# ADC_DAC_Supply.net
KiCad netlist of a schematic drawn in Altium Designer
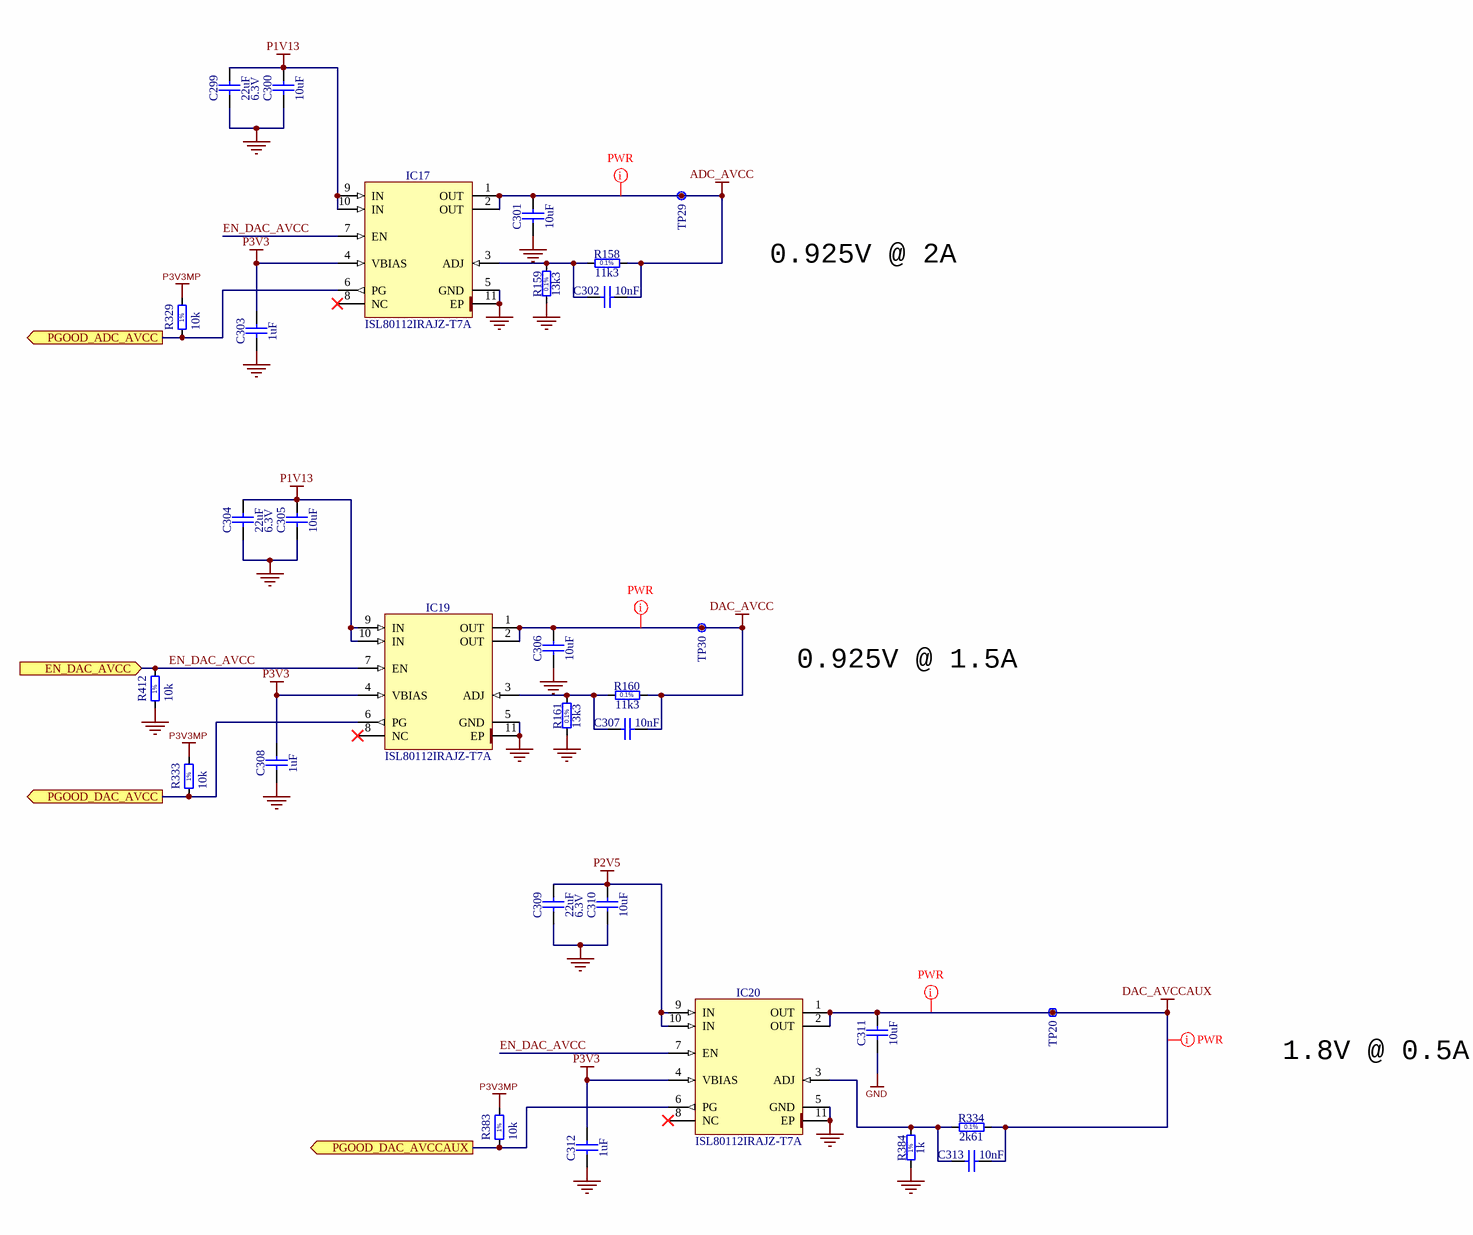
[diagram p0: ADC_DAC_Supply.SchDoc]

(export (version "E")
  (design (tool "Eeschema 10.0.6"))
  (components
    (comp (ref "C299")
      (value "22uF")
      (footprint "CAPC1709X100N")
      (description "Non-polarised capacitor")
      (fields
        (field (name "PART NUMBER") "CC0603_22UF_6.3V_20%_X5R")
        (field (name "VOLTAGE") "6.3V")
        (field (name "TOLERANCE") "±20%")
        (field (name "AUTHOR") "CERN DEM JLC")
      )
      (libsource (lib "Capacitors") (part "Capacitor - non polarized"))
    )
    (comp (ref "C300")
      (value "10uF")
      (footprint "CAPC1608X80N")
      (description "Non-polarised capacitor")
      (fields
        (field (name "PART NUMBER") "CC0603_10UF_10V_10%_X5R")
        (field (name "VOLTAGE") "10V")
        (field (name "AUTHOR") "CERN DEM JLC")
      )
      (libsource (lib "Capacitors") (part "Capacitor - non polarized"))
    )
    (comp (ref "C301")
      (value "10uF")
      (footprint "CAPC1608X80N")
      (description "Non-polarised capacitor")
      (fields
        (field (name "PART NUMBER") "CC0603_10UF_10V_10%_X5R")
        (field (name "VOLTAGE") "10V")
        (field (name "AUTHOR") "CERN DEM JLC")
      )
      (libsource (lib "Capacitors") (part "Capacitor - non polarized"))
    )
    (comp (ref "C302")
      (value "10nF")
      (footprint "CAPC1005X55N")
      (description "Non-polarised capacitor")
      (fields
        (field (name "PART NUMBER") "CC0402_10NF_25V_10%_X7R")
        (field (name "VOLTAGE") "25V")
        (field (name "AUTHOR") "CERN DEM JLC")
      )
      (libsource (lib "Capacitors") (part "Capacitor - non polarized"))
    )
    (comp (ref "C303")
      (value "1uF")
      (footprint "CAPC1005X55N")
      (description "Non-polarised capacitor")
      (fields
        (field (name "PART NUMBER") "CC0402_1UF_16V_10%_X5R")
        (field (name "VOLTAGE") "16V")
        (field (name "AUTHOR") "CERN DEM JLC")
      )
      (libsource (lib "Capacitors") (part "Capacitor - non polarized"))
    )
    (comp (ref "C304")
      (value "22uF")
      (footprint "CAPC1709X100N")
      (description "Non-polarised capacitor")
      (fields
        (field (name "PART NUMBER") "CC0603_22UF_6.3V_20%_X5R")
        (field (name "VOLTAGE") "6.3V")
        (field (name "TOLERANCE") "±20%")
        (field (name "AUTHOR") "CERN DEM JLC")
      )
      (libsource (lib "Capacitors") (part "Capacitor - non polarized"))
    )
    (comp (ref "C305")
      (value "10uF")
      (footprint "CAPC1608X80N")
      (description "Non-polarised capacitor")
      (fields
        (field (name "PART NUMBER") "CC0603_10UF_10V_10%_X5R")
        (field (name "VOLTAGE") "10V")
        (field (name "AUTHOR") "CERN DEM JLC")
      )
      (libsource (lib "Capacitors") (part "Capacitor - non polarized"))
    )
    (comp (ref "C306")
      (value "10uF")
      (footprint "CAPC1608X80N")
      (description "Non-polarised capacitor")
      (fields
        (field (name "PART NUMBER") "CC0603_10UF_10V_10%_X5R")
        (field (name "VOLTAGE") "10V")
        (field (name "AUTHOR") "CERN DEM JLC")
      )
      (libsource (lib "Capacitors") (part "Capacitor - non polarized"))
    )
    (comp (ref "C307")
      (value "10nF")
      (footprint "CAPC1005X55N")
      (description "Non-polarised capacitor")
      (fields
        (field (name "PART NUMBER") "CC0402_10NF_25V_10%_X7R")
        (field (name "VOLTAGE") "25V")
        (field (name "AUTHOR") "CERN DEM JLC")
      )
      (libsource (lib "Capacitors") (part "Capacitor - non polarized"))
    )
    (comp (ref "C308")
      (value "1uF")
      (footprint "CAPC1005X55N")
      (description "Non-polarised capacitor")
      (fields
        (field (name "PART NUMBER") "CC0402_1UF_16V_10%_X5R")
        (field (name "VOLTAGE") "16V")
        (field (name "AUTHOR") "CERN DEM JLC")
      )
      (libsource (lib "Capacitors") (part "Capacitor - non polarized"))
    )
    (comp (ref "C309")
      (value "22uF")
      (footprint "CAPC1709X100N")
      (description "Non-polarised capacitor")
      (fields
        (field (name "PART NUMBER") "CC0603_22UF_6.3V_20%_X5R")
        (field (name "VOLTAGE") "6.3V")
        (field (name "TOLERANCE") "±20%")
        (field (name "AUTHOR") "CERN DEM JLC")
      )
      (libsource (lib "Capacitors") (part "Capacitor - non polarized"))
    )
    (comp (ref "C310")
      (value "10uF")
      (footprint "CAPC1608X80N")
      (description "Non-polarised capacitor")
      (fields
        (field (name "PART NUMBER") "CC0603_10UF_10V_10%_X5R")
        (field (name "VOLTAGE") "10V")
        (field (name "AUTHOR") "CERN DEM JLC")
      )
      (libsource (lib "Capacitors") (part "Capacitor - non polarized"))
    )
    (comp (ref "C311")
      (value "10uF")
      (footprint "CAPC1608X80N")
      (description "Non-polarised capacitor")
      (fields
        (field (name "PART NUMBER") "CC0603_10UF_10V_10%_X5R")
        (field (name "VOLTAGE") "10V")
        (field (name "AUTHOR") "CERN DEM JLC")
      )
      (libsource (lib "Capacitors") (part "Capacitor - non polarized"))
    )
    (comp (ref "C312")
      (value "1uF")
      (footprint "CAPC1005X55N")
      (description "Non-polarised capacitor")
      (fields
        (field (name "PART NUMBER") "CC0402_1UF_16V_10%_X5R")
        (field (name "VOLTAGE") "16V")
        (field (name "AUTHOR") "CERN DEM JLC")
      )
      (libsource (lib "Capacitors") (part "Capacitor - non polarized"))
    )
    (comp (ref "C313")
      (value "10nF")
      (footprint "CAPC1005X55N")
      (description "Non-polarised capacitor")
      (fields
        (field (name "PART NUMBER") "CC0402_10NF_25V_10%_X7R")
        (field (name "VOLTAGE") "25V")
        (field (name "AUTHOR") "CERN DEM JLC")
      )
      (libsource (lib "Capacitors") (part "Capacitor - non polarized"))
    )
    (comp (ref "IC17")
      (value "ISL80112IRAJZ-T7A")
      (footprint "RENESAS_L10.3X3")
      (description "Ultra Low Dropout Low Input Voltage NMOS LDO Regulator")
      (fields (field (name "MANUFACTURER") "RENESAS ELECTRONICS") (field (name "AUTHOR") "CERN DEM JLC"))
      (libsource (lib "ICs And Semiconductors") (part "ISL8011x"))
    )
    (comp (ref "IC19")
      (value "ISL80112IRAJZ-T7A")
      (footprint "RENESAS_L10.3X3")
      (description "Ultra Low Dropout Low Input Voltage NMOS LDO Regulator")
      (fields (field (name "MANUFACTURER") "RENESAS ELECTRONICS") (field (name "AUTHOR") "CERN DEM JLC"))
      (libsource (lib "ICs And Semiconductors") (part "ISL8011x"))
    )
    (comp (ref "IC20")
      (value "ISL80112IRAJZ-T7A")
      (footprint "RENESAS_L10.3X3")
      (description "Ultra Low Dropout Low Input Voltage NMOS LDO Regulator")
      (fields (field (name "MANUFACTURER") "RENESAS ELECTRONICS") (field (name "AUTHOR") "CERN DEM JLC"))
      (libsource (lib "ICs And Semiconductors") (part "ISL8011x"))
    )
    (comp (ref "R158")
      (value "11k3")
      (footprint "RESC2012X60N")
      (description "Resistor - 0.1%")
      (fields
        (field (name "PART NUMBER") "R0805_11K3_0.1%_0.1W_10PPM")
        (field (name "POWER") "0.1W")
        (field (name "AUTHOR") "CERN DEM JLC")
      )
      (libsource (lib "Resistors") (part "Resistor - 0.1%"))
    )
    (comp (ref "R159")
      (value "13k3")
      (footprint "RESC2012X60N")
      (description "Resistor - 0.1%")
      (fields
        (field (name "PART NUMBER") "R0805_13K3_0.1%_0.1W_10PPM")
        (field (name "POWER") "0.1W")
        (field (name "AUTHOR") "CERN DEM JLC")
      )
      (libsource (lib "Resistors") (part "Resistor - 0.1%"))
    )
    (comp (ref "R160")
      (value "11k3")
      (footprint "RESC2012X60N")
      (description "Resistor - 0.1%")
      (fields
        (field (name "PART NUMBER") "R0805_11K3_0.1%_0.1W_10PPM")
        (field (name "POWER") "0.1W")
        (field (name "AUTHOR") "CERN DEM JLC")
      )
      (libsource (lib "Resistors") (part "Resistor - 0.1%"))
    )
    (comp (ref "R161")
      (value "13k3")
      (footprint "RESC2012X60N")
      (description "Resistor - 0.1%")
      (fields
        (field (name "PART NUMBER") "R0805_13K3_0.1%_0.1W_10PPM")
        (field (name "POWER") "0.1W")
        (field (name "AUTHOR") "CERN DEM JLC")
      )
      (libsource (lib "Resistors") (part "Resistor - 0.1%"))
    )
    (comp (ref "R329")
      (value "10k")
      (footprint "RESC1005X40N")
      (description "Resistor - 1%")
      (fields
        (field (name "MANUFACTURER PART NUMBER") "R0402_10K_1%_0.0625W_100PPM")
        (field (name "MANUFACTURER") "GENERIC")
        (field (name "AUTHOR") "CERN DEM JLC")
      )
      (libsource (lib "Resistors") (part "Resistor - 1%"))
    )
    (comp (ref "R333")
      (value "10k")
      (footprint "RESC1005X40N")
      (description "Resistor - 1%")
      (fields
        (field (name "MANUFACTURER PART NUMBER") "R0402_10K_1%_0.0625W_100PPM")
        (field (name "MANUFACTURER") "GENERIC")
        (field (name "AUTHOR") "CERN DEM JLC")
      )
      (libsource (lib "Resistors") (part "Resistor - 1%"))
    )
    (comp (ref "R334")
      (value "2k61")
      (footprint "RESC1608X55N")
      (description "Resistor - 0.1%")
      (fields
        (field (name "PART NUMBER") "R0603_2K61_0.1%_0.063W_10PPM")
        (field (name "POWER") "0.063W")
        (field (name "AUTHOR") "CERN DEM JLC")
      )
      (libsource (lib "Resistors") (part "Resistor - 0.1%"))
    )
    (comp (ref "R383")
      (value "10k")
      (footprint "RESC1005X40N")
      (description "Resistor - 1%")
      (fields
        (field (name "MANUFACTURER PART NUMBER") "R0402_10K_1%_0.0625W_100PPM")
        (field (name "MANUFACTURER") "GENERIC")
        (field (name "AUTHOR") "CERN DEM JLC")
      )
      (libsource (lib "Resistors") (part "Resistor - 1%"))
    )
    (comp (ref "R384")
      (value "1k")
      (footprint "RESC1608X55N")
      (description "Resistor - 1%")
      (fields
        (field (name "PART NUMBER") "R0603_1K_1%_0.1W_100PPM")
        (field (name "POWER") "0.1W")
        (field (name "AUTHOR") "CERN DEM JLC")
      )
      (libsource (lib "Resistors") (part "Resistor - 1%"))
    )
    (comp (ref "R412")
      (value "10k")
      (footprint "RESC1005X40N")
      (description "Resistor - 1%")
      (fields
        (field (name "MANUFACTURER PART NUMBER") "R0402_10K_1%_0.0625W_100PPM")
        (field (name "MANUFACTURER") "GENERIC")
        (field (name "AUTHOR") "CERN DEM JLC")
      )
      (libsource (lib "Resistors") (part "Resistor - 1%"))
    )
    (comp (ref "TP20")
      (value "Test Point")
      (footprint "TPS127")
      (fields (field (name "PART NUMBER") "SMD_PAD_1.27X1.27MM") (field (name "AUTHOR") "CERN DEM JLC"))
      (libsource (lib "Eletro-mechanical") (part "Test Point"))
    )
    (comp (ref "TP29")
      (value "Test Point")
      (footprint "TPS127")
      (fields (field (name "PART NUMBER") "SMD_PAD_1.27X1.27MM") (field (name "AUTHOR") "CERN DEM JLC"))
      (libsource (lib "Eletro-mechanical") (part "Test Point"))
    )
    (comp (ref "TP30")
      (value "Test Point")
      (footprint "TPS127")
      (fields (field (name "PART NUMBER") "SMD_PAD_1.27X1.27MM") (field (name "AUTHOR") "CERN DEM JLC"))
      (libsource (lib "Eletro-mechanical") (part "Test Point"))
    )
  )
  (nets
    (net (code "1") (name "/EN_DAC_AVCC") (class "Default")
      (node (ref "IC17") (pin "7") (pinfunction "EN_7") (pintype "input"))
      (node (ref "IC19") (pin "7") (pinfunction "EN_7") (pintype "input"))
      (node (ref "IC20") (pin "7") (pinfunction "EN_7") (pintype "input"))
      (node (ref "R412") (pin "2") (pinfunction "2_2") (pintype "passive"))
    )
    (net (code "2") (name "/PGOOD_ADC_AVCC") (class "Default")
      (node (ref "IC17") (pin "6") (pinfunction "PG_6") (pintype "output"))
      (node (ref "R329") (pin "1") (pinfunction "1_1") (pintype "passive"))
    )
    (net (code "3") (name "/PGOOD_DAC_AVCC") (class "Default")
      (node (ref "IC19") (pin "6") (pinfunction "PG_6") (pintype "output"))
      (node (ref "R333") (pin "1") (pinfunction "1_1") (pintype "passive"))
    )
    (net (code "4") (name "/PGOOD_DAC_AVCCAUX") (class "Default")
      (node (ref "IC20") (pin "6") (pinfunction "PG_6") (pintype "output"))
      (node (ref "R383") (pin "1") (pinfunction "1_1") (pintype "passive"))
    )
    (net (code "5") (name "ADC_AVCC") (class "Default")
      (node (ref "C301") (pin "2") (pinfunction "2_2") (pintype "passive"))
      (node (ref "C302") (pin "2") (pinfunction "2_2") (pintype "passive"))
      (node (ref "IC17") (pin "1") (pinfunction "OUT_1") (pintype "power_in"))
      (node (ref "IC17") (pin "2") (pinfunction "OUT_2") (pintype "power_in"))
      (node (ref "R158") (pin "2") (pinfunction "2_2") (pintype "passive"))
      (node (ref "TP29") (pin "1") (pinfunction "1_1") (pintype "bidirectional"))
    )
    (net (code "6") (name "DAC_AVCC") (class "Default")
      (node (ref "C306") (pin "2") (pinfunction "2_2") (pintype "passive"))
      (node (ref "C307") (pin "2") (pinfunction "2_2") (pintype "passive"))
      (node (ref "IC19") (pin "1") (pinfunction "OUT_1") (pintype "power_in"))
      (node (ref "IC19") (pin "2") (pinfunction "OUT_2") (pintype "power_in"))
      (node (ref "R160") (pin "2") (pinfunction "2_2") (pintype "passive"))
      (node (ref "TP30") (pin "1") (pinfunction "1_1") (pintype "bidirectional"))
    )
    (net (code "7") (name "DAC_AVCCAUX") (class "Default")
      (node (ref "C311") (pin "2") (pinfunction "2_2") (pintype "passive"))
      (node (ref "C313") (pin "2") (pinfunction "2_2") (pintype "passive"))
      (node (ref "IC20") (pin "1") (pinfunction "OUT_1") (pintype "power_in"))
      (node (ref "IC20") (pin "2") (pinfunction "OUT_2") (pintype "power_in"))
      (node (ref "R334") (pin "2") (pinfunction "2_2") (pintype "passive"))
      (node (ref "TP20") (pin "1") (pinfunction "1_1") (pintype "bidirectional"))
    )
    (net (code "8") (name "GND") (class "Default")
      (node (ref "C299") (pin "1") (pinfunction "1_1") (pintype "passive"))
      (node (ref "C300") (pin "1") (pinfunction "1_1") (pintype "passive"))
      (node (ref "C301") (pin "1") (pinfunction "1_1") (pintype "passive"))
      (node (ref "C303") (pin "1") (pinfunction "1_1") (pintype "passive"))
      (node (ref "C304") (pin "1") (pinfunction "1_1") (pintype "passive"))
      (node (ref "C305") (pin "1") (pinfunction "1_1") (pintype "passive"))
      (node (ref "C306") (pin "1") (pinfunction "1_1") (pintype "passive"))
      (node (ref "C308") (pin "1") (pinfunction "1_1") (pintype "passive"))
      (node (ref "C309") (pin "1") (pinfunction "1_1") (pintype "passive"))
      (node (ref "C310") (pin "1") (pinfunction "1_1") (pintype "passive"))
      (node (ref "C311") (pin "1") (pinfunction "1_1") (pintype "passive"))
      (node (ref "C312") (pin "1") (pinfunction "1_1") (pintype "passive"))
      (node (ref "IC17") (pin "11") (pinfunction "EP_11") (pintype "power_in"))
      (node (ref "IC17") (pin "5") (pinfunction "GND_5") (pintype "power_in"))
      (node (ref "IC19") (pin "11") (pinfunction "EP_11") (pintype "power_in"))
      (node (ref "IC19") (pin "5") (pinfunction "GND_5") (pintype "power_in"))
      (node (ref "IC20") (pin "11") (pinfunction "EP_11") (pintype "power_in"))
      (node (ref "IC20") (pin "5") (pinfunction "GND_5") (pintype "power_in"))
      (node (ref "R159") (pin "1") (pinfunction "1_1") (pintype "passive"))
      (node (ref "R161") (pin "1") (pinfunction "1_1") (pintype "passive"))
      (node (ref "R384") (pin "1") (pinfunction "1_1") (pintype "passive"))
      (node (ref "R412") (pin "1") (pinfunction "1_1") (pintype "passive"))
    )
    (net (code "9") (name "Net-(IC17-ADJ)") (class "Default")
      (node (ref "C302") (pin "1") (pinfunction "1_1") (pintype "passive"))
      (node (ref "IC17") (pin "3") (pinfunction "ADJ_3") (pintype "input"))
      (node (ref "R158") (pin "1") (pinfunction "1_1") (pintype "passive"))
      (node (ref "R159") (pin "2") (pinfunction "2_2") (pintype "passive"))
    )
    (net (code "10") (name "Net-(IC19-ADJ)") (class "Default")
      (node (ref "C307") (pin "1") (pinfunction "1_1") (pintype "passive"))
      (node (ref "IC19") (pin "3") (pinfunction "ADJ_3") (pintype "input"))
      (node (ref "R160") (pin "1") (pinfunction "1_1") (pintype "passive"))
      (node (ref "R161") (pin "2") (pinfunction "2_2") (pintype "passive"))
    )
    (net (code "11") (name "Net-(IC20-ADJ)") (class "Default")
      (node (ref "C313") (pin "1") (pinfunction "1_1") (pintype "passive"))
      (node (ref "IC20") (pin "3") (pinfunction "ADJ_3") (pintype "input"))
      (node (ref "R334") (pin "1") (pinfunction "1_1") (pintype "passive"))
      (node (ref "R384") (pin "2") (pinfunction "2_2") (pintype "passive"))
    )
    (net (code "12") (name "P1V13") (class "Default")
      (node (ref "C299") (pin "2") (pinfunction "2_2") (pintype "passive"))
      (node (ref "C300") (pin "2") (pinfunction "2_2") (pintype "passive"))
      (node (ref "C304") (pin "2") (pinfunction "2_2") (pintype "passive"))
      (node (ref "C305") (pin "2") (pinfunction "2_2") (pintype "passive"))
      (node (ref "IC17") (pin "10") (pinfunction "IN_10") (pintype "input"))
      (node (ref "IC17") (pin "9") (pinfunction "IN_9") (pintype "input"))
      (node (ref "IC19") (pin "10") (pinfunction "IN_10") (pintype "input"))
      (node (ref "IC19") (pin "9") (pinfunction "IN_9") (pintype "input"))
    )
    (net (code "13") (name "P2V5") (class "Default")
      (node (ref "C309") (pin "2") (pinfunction "2_2") (pintype "passive"))
      (node (ref "C310") (pin "2") (pinfunction "2_2") (pintype "passive"))
      (node (ref "IC20") (pin "10") (pinfunction "IN_10") (pintype "input"))
      (node (ref "IC20") (pin "9") (pinfunction "IN_9") (pintype "input"))
    )
    (net (code "14") (name "P3V3") (class "Default")
      (node (ref "C303") (pin "2") (pinfunction "2_2") (pintype "passive"))
      (node (ref "C308") (pin "2") (pinfunction "2_2") (pintype "passive"))
      (node (ref "C312") (pin "2") (pinfunction "2_2") (pintype "passive"))
      (node (ref "IC17") (pin "4") (pinfunction "VBIAS_4") (pintype "input"))
      (node (ref "IC19") (pin "4") (pinfunction "VBIAS_4") (pintype "input"))
      (node (ref "IC20") (pin "4") (pinfunction "VBIAS_4") (pintype "input"))
    )
    (net (code "15") (name "P3V3MP") (class "Default")
      (node (ref "R329") (pin "2") (pinfunction "2_2") (pintype "passive"))
      (node (ref "R333") (pin "2") (pinfunction "2_2") (pintype "passive"))
      (node (ref "R383") (pin "2") (pinfunction "2_2") (pintype "passive"))
    )
    (net (code "16") (name "unconnected-(IC17-NC-Pad8)") (class "Default")
      (node (ref "IC17") (pin "8") (pinfunction "NC_8") (pintype "passive+no_connect"))
    )
    (net (code "17") (name "unconnected-(IC19-NC-Pad8)") (class "Default")
      (node (ref "IC19") (pin "8") (pinfunction "NC_8") (pintype "passive+no_connect"))
    )
    (net (code "18") (name "unconnected-(IC20-NC-Pad8)") (class "Default")
      (node (ref "IC20") (pin "8") (pinfunction "NC_8") (pintype "passive+no_connect"))
    )
  )
)
